# StandaloneAnemometer_RevA.net
KiCad netlist of a schematic drawn in EAGLE
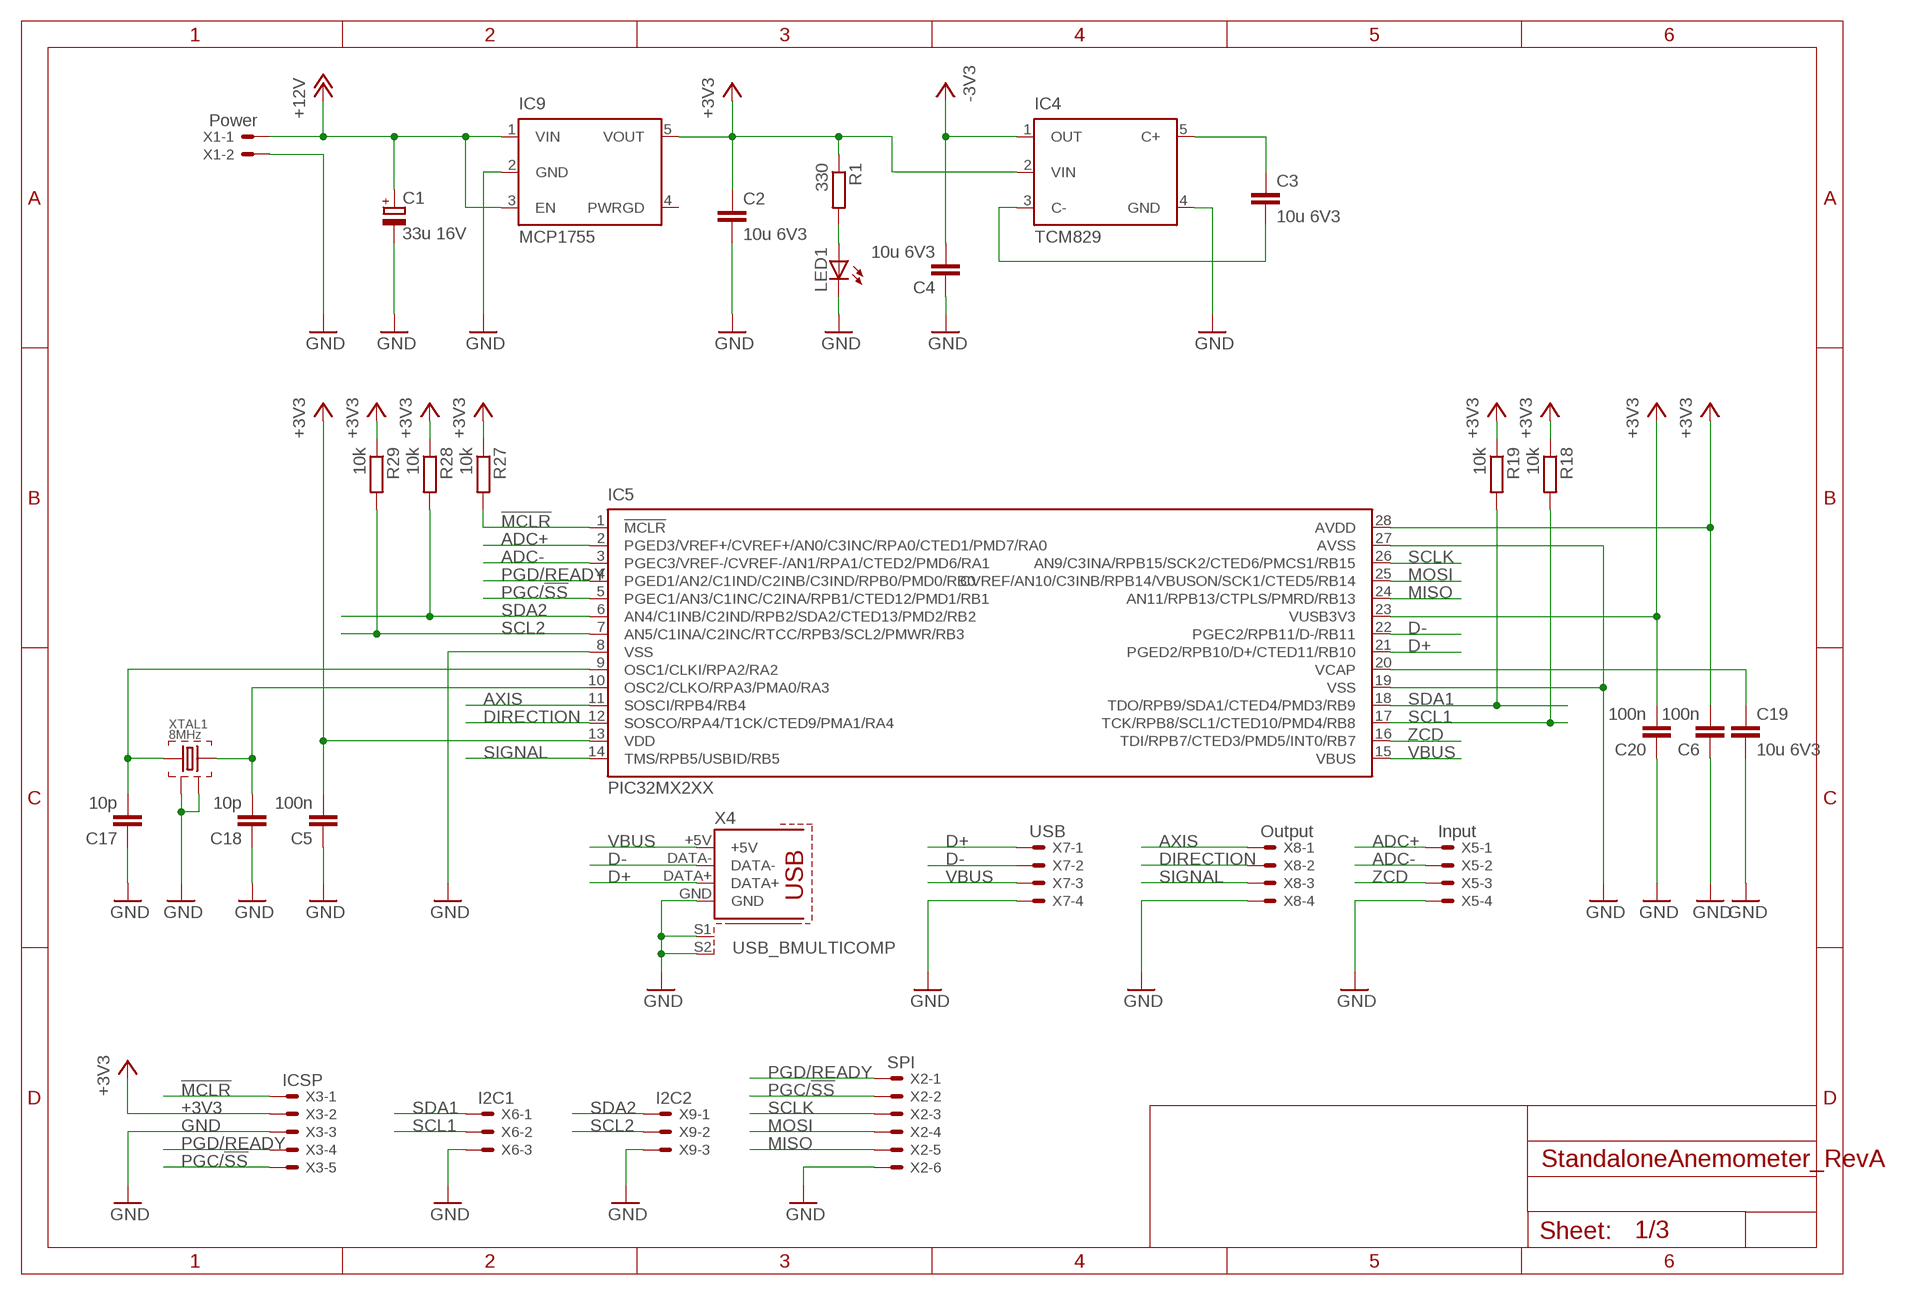
[diagram p0: schematic, sheet 1]
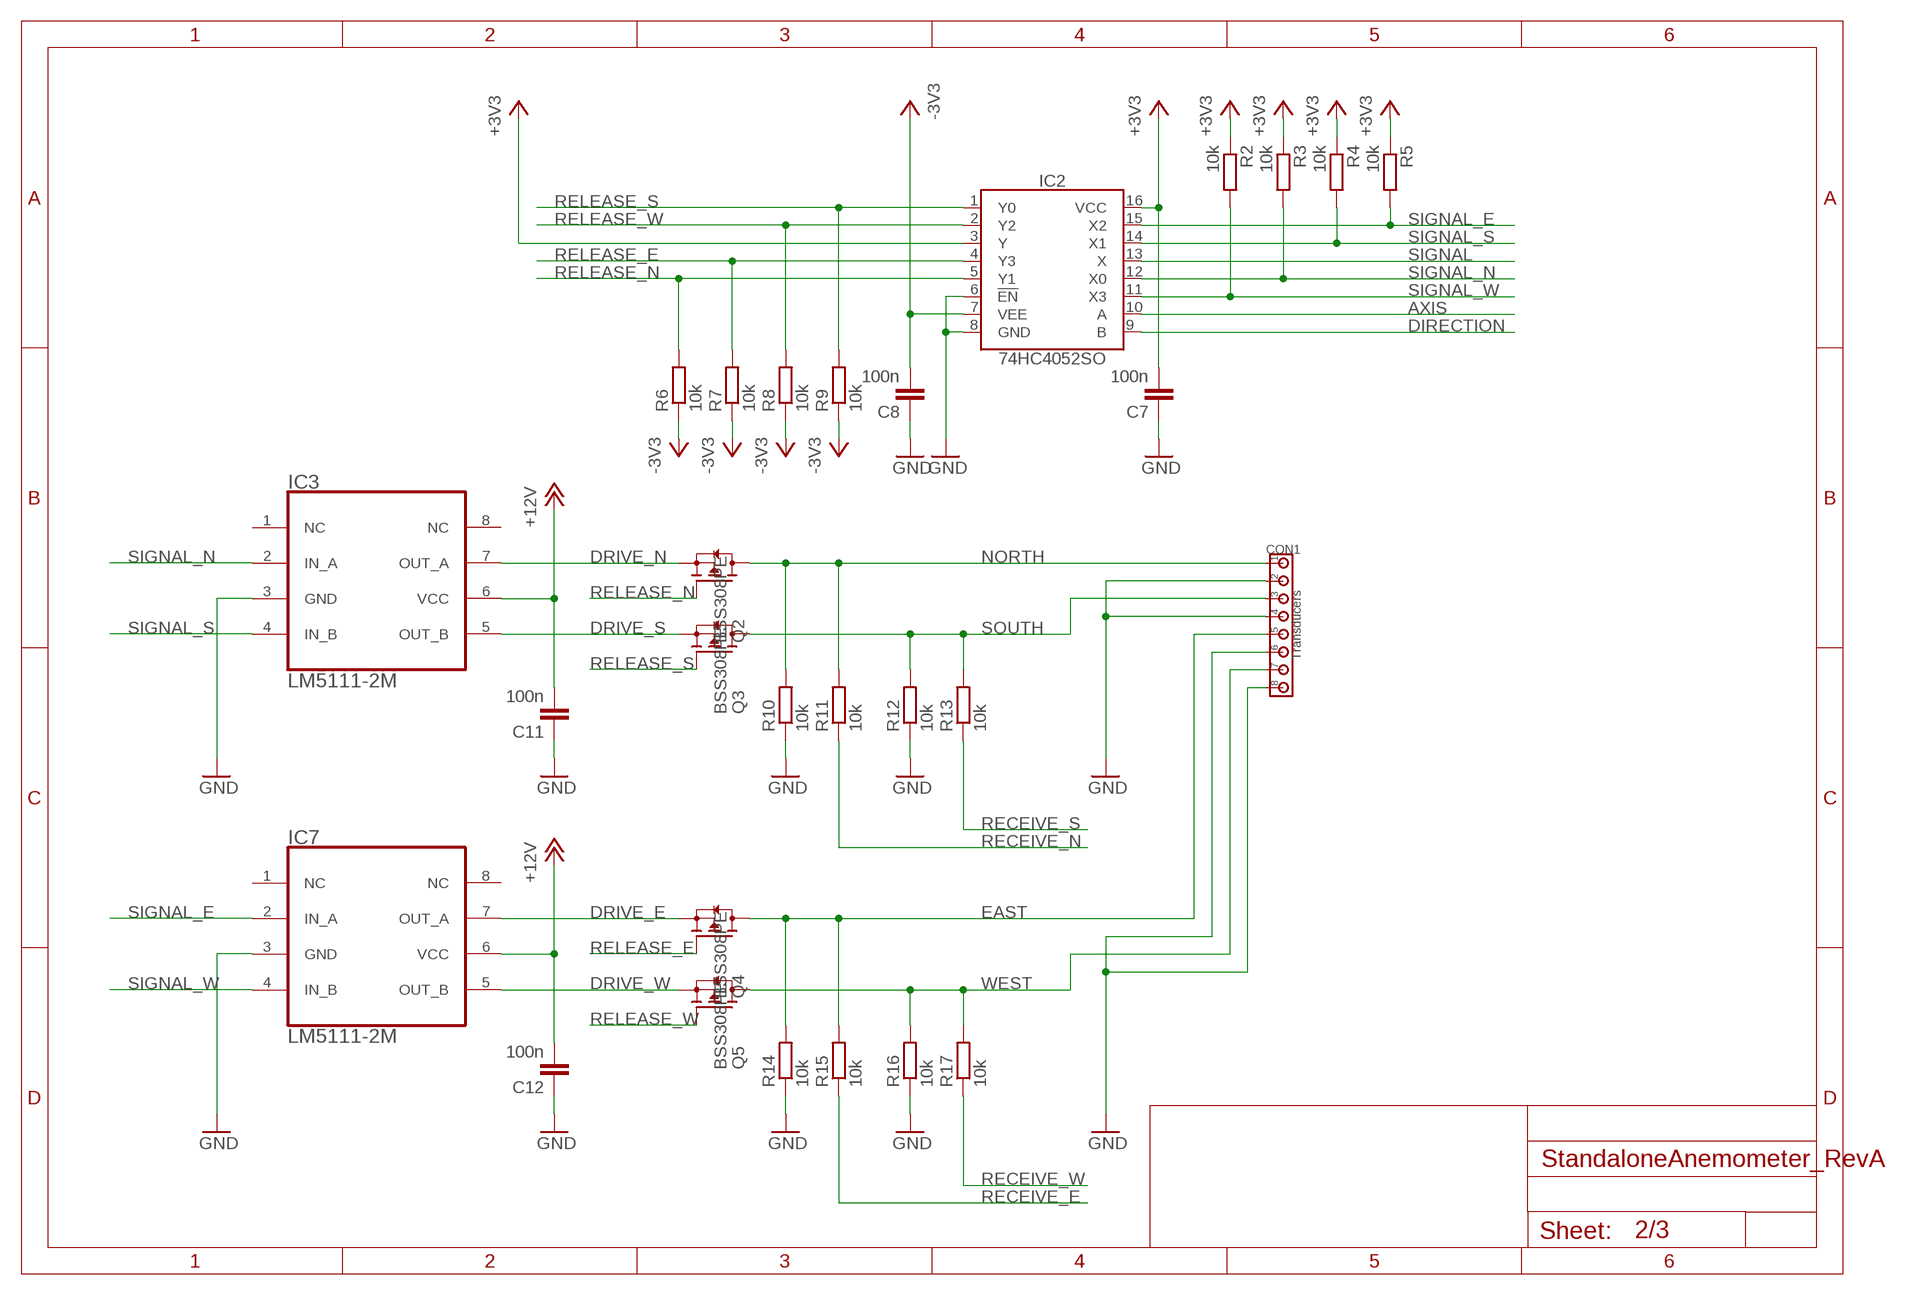
[diagram p1: schematic, sheet 2]
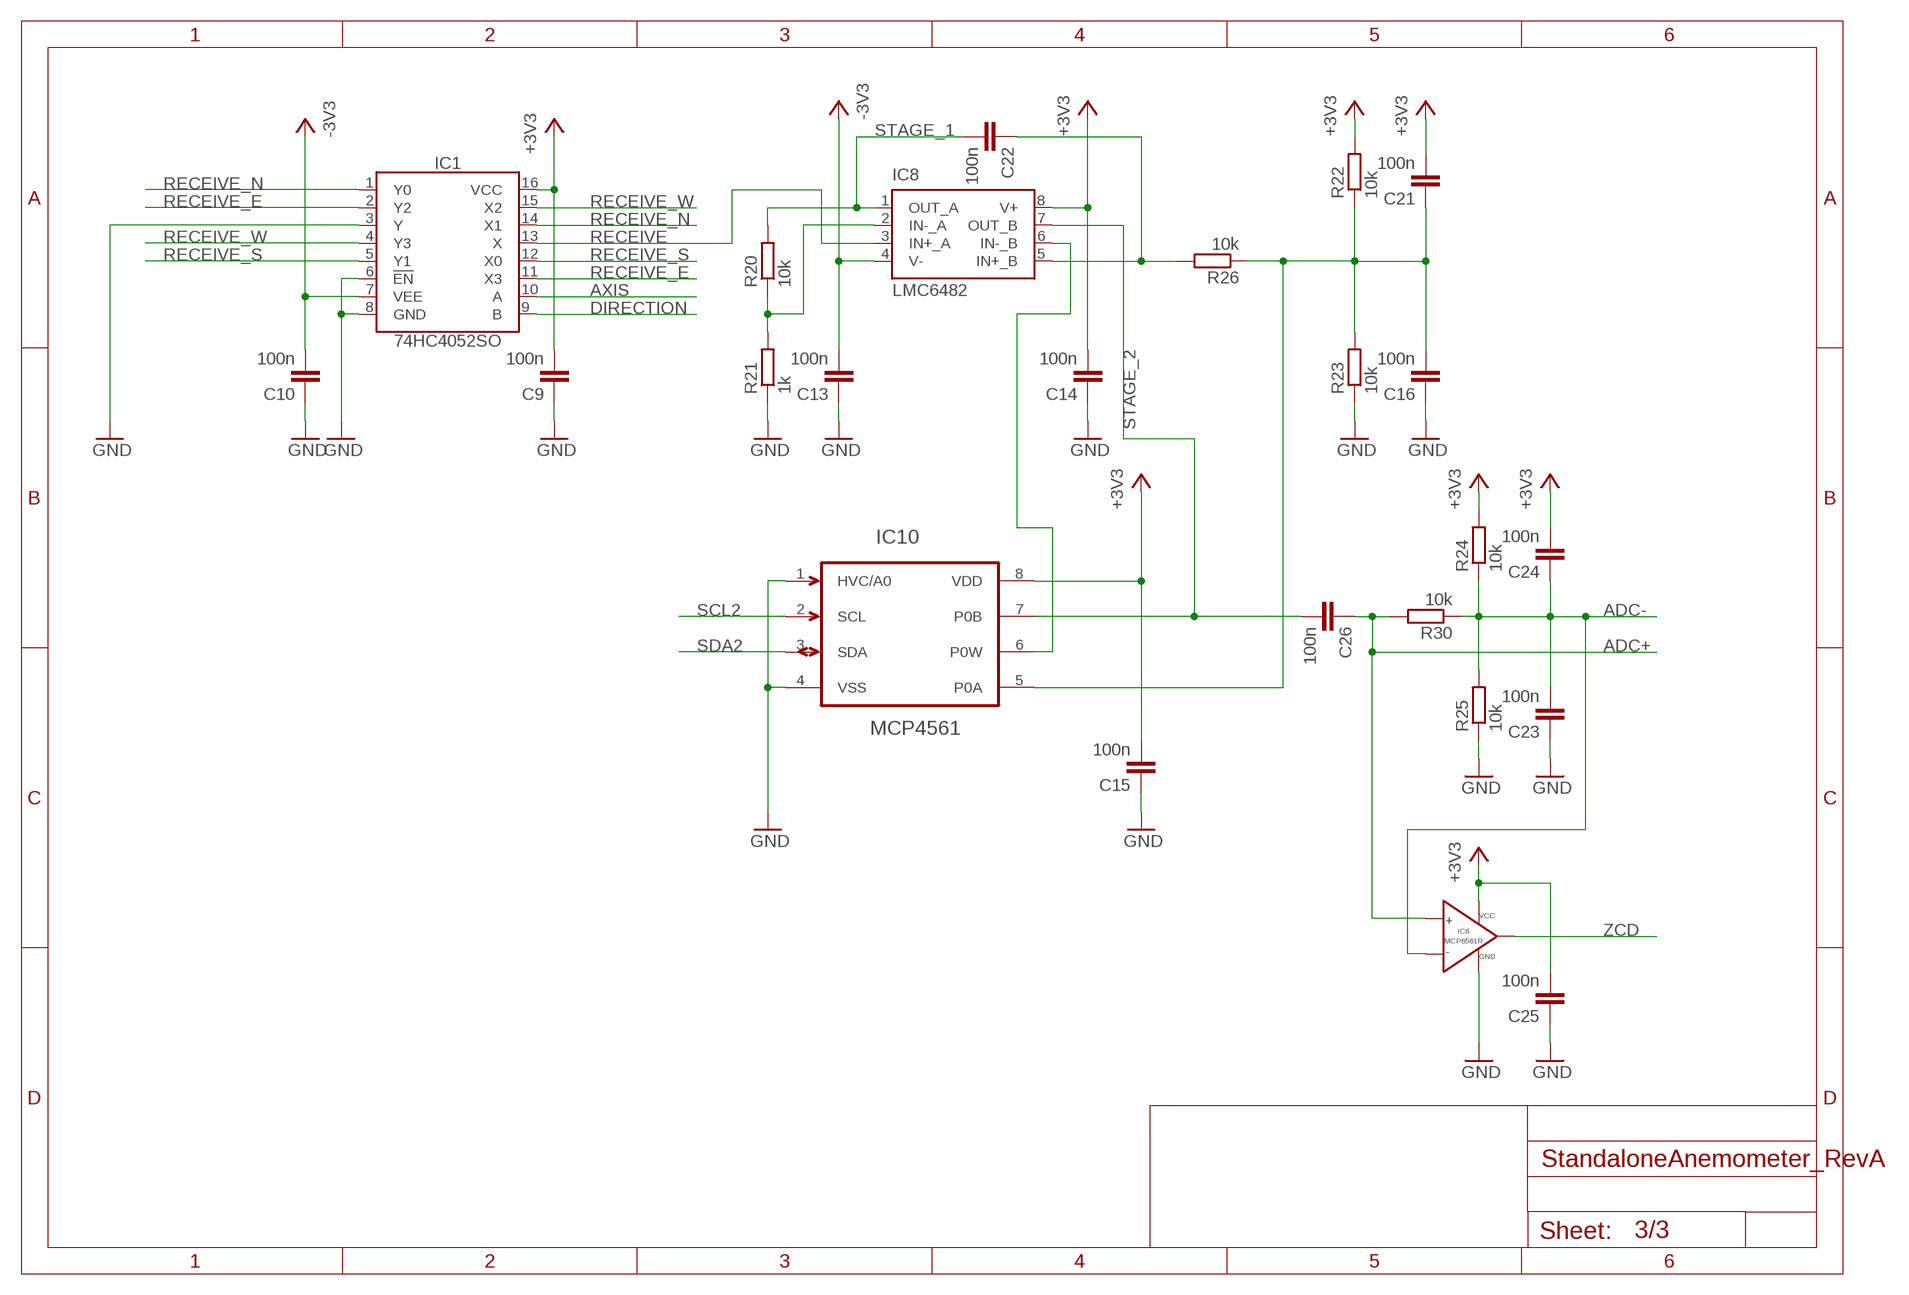
[diagram p2: schematic, sheet 3]

(export (version "E")
  (design (tool "Eeschema 10.0.6"))
  (components
    (comp (ref "C1")
      (value "33u 16V")
      (footprint "eagle-import:SMC_B")
      (libsource (lib "eagle-import") (part "C_POLARIZEDSMC_B"))
    )
    (comp (ref "C2")
      (value "10u 6V3")
      (footprint "eagle-import:C0805")
      (libsource (lib "eagle-import") (part "CC0805"))
    )
    (comp (ref "C3")
      (value "10u 6V3")
      (footprint "eagle-import:C0805")
      (libsource (lib "eagle-import") (part "CC0805"))
    )
    (comp (ref "C4")
      (value "10u 6V3")
      (footprint "eagle-import:C0805")
      (libsource (lib "eagle-import") (part "CC0805"))
    )
    (comp (ref "C5")
      (value "100n")
      (footprint "eagle-import:C0805")
      (libsource (lib "eagle-import") (part "CC0805"))
    )
    (comp (ref "C6")
      (value "100n")
      (footprint "eagle-import:C0805")
      (libsource (lib "eagle-import") (part "CC0805"))
    )
    (comp (ref "C17")
      (value "10p")
      (footprint "eagle-import:C0805")
      (libsource (lib "eagle-import") (part "CC0805"))
    )
    (comp (ref "C18")
      (value "10p")
      (footprint "eagle-import:C0805")
      (libsource (lib "eagle-import") (part "CC0805"))
    )
    (comp (ref "C19")
      (value "10u 6V3")
      (footprint "eagle-import:C0805")
      (libsource (lib "eagle-import") (part "CC0805"))
    )
    (comp (ref "C20")
      (value "100n")
      (footprint "eagle-import:C0805")
      (libsource (lib "eagle-import") (part "CC0805"))
    )
    (comp (ref "IC4")
      (value "TCM829")
      (footprint "eagle-import:SOT-23-5")
      (libsource (lib "eagle-import") (part "TCM829"))
    )
    (comp (ref "IC5")
      (value "PIC32MX2XX")
      (footprint "eagle-import:SO28W")
      (libsource (lib "eagle-import") (part "PIC32MX2XX"))
    )
    (comp (ref "IC9")
      (value "MCP1755")
      (footprint "eagle-import:SOT-23-5")
      (libsource (lib "eagle-import") (part "MCP1755"))
    )
    (comp (ref "LED1")
      (value "LED0805")
      (footprint "eagle-import:LED0805")
      (libsource (lib "eagle-import") (part "LED0805"))
    )
    (comp (ref "R1")
      (value "330")
      (footprint "eagle-import:R0805")
      (libsource (lib "eagle-import") (part "RESISTORR0805"))
    )
    (comp (ref "R18")
      (value "10k")
      (footprint "eagle-import:R0805")
      (libsource (lib "eagle-import") (part "RESISTORR0805"))
    )
    (comp (ref "R19")
      (value "10k")
      (footprint "eagle-import:R0805")
      (libsource (lib "eagle-import") (part "RESISTORR0805"))
    )
    (comp (ref "R27")
      (value "10k")
      (footprint "eagle-import:R0805")
      (libsource (lib "eagle-import") (part "RESISTORR0805"))
    )
    (comp (ref "R28")
      (value "10k")
      (footprint "eagle-import:R0805")
      (libsource (lib "eagle-import") (part "RESISTORR0805"))
    )
    (comp (ref "R29")
      (value "10k")
      (footprint "eagle-import:R0805")
      (libsource (lib "eagle-import") (part "RESISTORR0805"))
    )
    (comp (ref "X1")
      (value "Power")
      (footprint "eagle-import:22-23-2021")
      (fields (field (name "MF") "MOLEX") (field (name "MPN") "22-23-2021"))
      (libsource (lib "eagle-import") (part "22-23-2021100MIL"))
    )
    (comp (ref "X2")
      (value "SPI")
      (footprint "eagle-import:22-23-2061")
      (fields (field (name "MF") "MOLEX") (field (name "MPN") "22-23-2061"))
      (libsource (lib "eagle-import") (part "22-23-2061"))
    )
    (comp (ref "X3")
      (value "ICSP")
      (footprint "eagle-import:22-23-2051")
      (fields (field (name "MF") "MOLEX") (field (name "MPN") "22-23-2051"))
      (libsource (lib "eagle-import") (part "22-23-2051"))
    )
    (comp (ref "X4")
      (value "USB_BMULTICOMP")
      (footprint "eagle-import:USB_B")
      (libsource (lib "eagle-import") (part "USB_BMULTICOMP"))
    )
    (comp (ref "X5")
      (value "Input")
      (footprint "eagle-import:22-23-2041")
      (libsource (lib "eagle-import") (part "22-23-20411MM"))
    )
    (comp (ref "X6")
      (value "I2C1")
      (footprint "eagle-import:22-23-2031")
      (fields (field (name "MF") "MOLEX") (field (name "MPN") "22-23-2031"))
      (libsource (lib "eagle-import") (part "22-23-2031"))
    )
    (comp (ref "X7")
      (value "USB")
      (footprint "eagle-import:22-23-2041")
      (libsource (lib "eagle-import") (part "22-23-20411MM"))
    )
    (comp (ref "X8")
      (value "Output")
      (footprint "eagle-import:22-23-2041")
      (libsource (lib "eagle-import") (part "22-23-20411MM"))
    )
    (comp (ref "X9")
      (value "I2C2")
      (footprint "eagle-import:22-23-2031")
      (fields (field (name "MF") "MOLEX") (field (name "MPN") "22-23-2031"))
      (libsource (lib "eagle-import") (part "22-23-2031"))
    )
    (comp (ref "XTAL1")
      (value "8MHz")
      (footprint "eagle-import:5X3.2MM")
      (libsource (lib "eagle-import") (part "CRYSTAL_SHIELDED"))
    )
    (comp (ref "C9")
      (value "100n")
      (footprint "eagle-import:C0805")
      (libsource (lib "eagle-import") (part "CC0805"))
    )
    (comp (ref "C10")
      (value "100n")
      (footprint "eagle-import:C0805")
      (libsource (lib "eagle-import") (part "CC0805"))
    )
    (comp (ref "C13")
      (value "100n")
      (footprint "eagle-import:C0805")
      (libsource (lib "eagle-import") (part "CC0805"))
    )
    (comp (ref "C14")
      (value "100n")
      (footprint "eagle-import:C0805")
      (libsource (lib "eagle-import") (part "CC0805"))
    )
    (comp (ref "C15")
      (value "100n")
      (footprint "eagle-import:C0805")
      (libsource (lib "eagle-import") (part "CC0805"))
    )
    (comp (ref "C16")
      (value "100n")
      (footprint "eagle-import:C0805")
      (libsource (lib "eagle-import") (part "CC0805"))
    )
    (comp (ref "C21")
      (value "100n")
      (footprint "eagle-import:C0805")
      (libsource (lib "eagle-import") (part "CC0805"))
    )
    (comp (ref "C22")
      (value "100n")
      (footprint "eagle-import:C0805")
      (libsource (lib "eagle-import") (part "CC0805"))
    )
    (comp (ref "C23")
      (value "100n")
      (footprint "eagle-import:C0805")
      (libsource (lib "eagle-import") (part "CC0805"))
    )
    (comp (ref "C24")
      (value "100n")
      (footprint "eagle-import:C0805")
      (libsource (lib "eagle-import") (part "CC0805"))
    )
    (comp (ref "C25")
      (value "100n")
      (footprint "eagle-import:C0805")
      (libsource (lib "eagle-import") (part "CC0805"))
    )
    (comp (ref "C26")
      (value "100n")
      (footprint "eagle-import:C0805")
      (libsource (lib "eagle-import") (part "CC0805"))
    )
    (comp (ref "IC1")
      (value "74HC4052SO")
      (footprint "eagle-import:SO16")
      (libsource (lib "eagle-import") (part "74HC4052SO"))
    )
    (comp (ref "IC6")
      (value "MCP6561R")
      (footprint "eagle-import:SOT-23-5")
      (libsource (lib "eagle-import") (part "MCP6561R"))
    )
    (comp (ref "IC8")
      (value "LMC6482")
      (footprint "eagle-import:SOIC8")
      (libsource (lib "eagle-import") (part "LMC6482"))
    )
    (comp (ref "IC10")
      (value "MCP4561")
      (footprint "eagle-import:MSOP")
      (libsource (lib "eagle-import") (part "MCP4561MSOP"))
    )
    (comp (ref "R20")
      (value "10k")
      (footprint "eagle-import:R0805")
      (libsource (lib "eagle-import") (part "RESISTORR0805"))
    )
    (comp (ref "R21")
      (value "1k")
      (footprint "eagle-import:R0805")
      (libsource (lib "eagle-import") (part "RESISTORR0805"))
    )
    (comp (ref "R22")
      (value "10k")
      (footprint "eagle-import:R0805")
      (libsource (lib "eagle-import") (part "RESISTORR0805"))
    )
    (comp (ref "R23")
      (value "10k")
      (footprint "eagle-import:R0805")
      (libsource (lib "eagle-import") (part "RESISTORR0805"))
    )
    (comp (ref "R24")
      (value "10k")
      (footprint "eagle-import:R0805")
      (libsource (lib "eagle-import") (part "RESISTORR0805"))
    )
    (comp (ref "R25")
      (value "10k")
      (footprint "eagle-import:R0805")
      (libsource (lib "eagle-import") (part "RESISTORR0805"))
    )
    (comp (ref "R26")
      (value "10k")
      (footprint "eagle-import:R0805")
      (libsource (lib "eagle-import") (part "RESISTORR0805"))
    )
    (comp (ref "R30")
      (value "10k")
      (footprint "eagle-import:R0805")
      (libsource (lib "eagle-import") (part "RESISTORR0805"))
    )
    (comp (ref "C7")
      (value "100n")
      (footprint "eagle-import:C0805")
      (libsource (lib "eagle-import") (part "CC0805"))
    )
    (comp (ref "C8")
      (value "100n")
      (footprint "eagle-import:C0805")
      (libsource (lib "eagle-import") (part "CC0805"))
    )
    (comp (ref "C11")
      (value "100n")
      (footprint "eagle-import:C0805")
      (libsource (lib "eagle-import") (part "CC0805"))
    )
    (comp (ref "C12")
      (value "100n")
      (footprint "eagle-import:C0805")
      (libsource (lib "eagle-import") (part "CC0805"))
    )
    (comp (ref "CON1")
      (value "Transducers")
      (footprint "eagle-import:3.5MM_8X")
      (libsource (lib "eagle-import") (part "CON_8X3.5MM"))
    )
    (comp (ref "IC2")
      (value "74HC4052SO")
      (footprint "eagle-import:SO16")
      (libsource (lib "eagle-import") (part "74HC4052SO"))
    )
    (comp (ref "IC3")
      (value "LM5111-2M")
      (footprint "eagle-import:SOIC8")
      (libsource (lib "eagle-import") (part "LM5111"))
    )
    (comp (ref "IC7")
      (value "LM5111-2M")
      (footprint "eagle-import:SOIC8")
      (libsource (lib "eagle-import") (part "LM5111"))
    )
    (comp (ref "Q2")
      (value "BSS308PE")
      (footprint "eagle-import:SOT23")
      (libsource (lib "eagle-import") (part "P-FET"))
    )
    (comp (ref "Q3")
      (value "BSS308PE")
      (footprint "eagle-import:SOT23")
      (libsource (lib "eagle-import") (part "P-FET"))
    )
    (comp (ref "Q4")
      (value "BSS308PE")
      (footprint "eagle-import:SOT23")
      (libsource (lib "eagle-import") (part "P-FET"))
    )
    (comp (ref "Q5")
      (value "BSS308PE")
      (footprint "eagle-import:SOT23")
      (libsource (lib "eagle-import") (part "P-FET"))
    )
    (comp (ref "R2")
      (value "10k")
      (footprint "eagle-import:R0805")
      (libsource (lib "eagle-import") (part "RESISTORR0805"))
    )
    (comp (ref "R3")
      (value "10k")
      (footprint "eagle-import:R0805")
      (libsource (lib "eagle-import") (part "RESISTORR0805"))
    )
    (comp (ref "R4")
      (value "10k")
      (footprint "eagle-import:R0805")
      (libsource (lib "eagle-import") (part "RESISTORR0805"))
    )
    (comp (ref "R5")
      (value "10k")
      (footprint "eagle-import:R0805")
      (libsource (lib "eagle-import") (part "RESISTORR0805"))
    )
    (comp (ref "R6")
      (value "10k")
      (footprint "eagle-import:R0805")
      (libsource (lib "eagle-import") (part "RESISTORR0805"))
    )
    (comp (ref "R7")
      (value "10k")
      (footprint "eagle-import:R0805")
      (libsource (lib "eagle-import") (part "RESISTORR0805"))
    )
    (comp (ref "R8")
      (value "10k")
      (footprint "eagle-import:R0805")
      (libsource (lib "eagle-import") (part "RESISTORR0805"))
    )
    (comp (ref "R9")
      (value "10k")
      (footprint "eagle-import:R0805")
      (libsource (lib "eagle-import") (part "RESISTORR0805"))
    )
    (comp (ref "R10")
      (value "10k")
      (footprint "eagle-import:R0805")
      (libsource (lib "eagle-import") (part "RESISTORR0805"))
    )
    (comp (ref "R11")
      (value "10k")
      (footprint "eagle-import:R0805")
      (libsource (lib "eagle-import") (part "RESISTORR0805"))
    )
    (comp (ref "R12")
      (value "10k")
      (footprint "eagle-import:R0805")
      (libsource (lib "eagle-import") (part "RESISTORR0805"))
    )
    (comp (ref "R13")
      (value "10k")
      (footprint "eagle-import:R0805")
      (libsource (lib "eagle-import") (part "RESISTORR0805"))
    )
    (comp (ref "R14")
      (value "10k")
      (footprint "eagle-import:R0805")
      (libsource (lib "eagle-import") (part "RESISTORR0805"))
    )
    (comp (ref "R15")
      (value "10k")
      (footprint "eagle-import:R0805")
      (libsource (lib "eagle-import") (part "RESISTORR0805"))
    )
    (comp (ref "R16")
      (value "10k")
      (footprint "eagle-import:R0805")
      (libsource (lib "eagle-import") (part "RESISTORR0805"))
    )
    (comp (ref "R17")
      (value "10k")
      (footprint "eagle-import:R0805")
      (libsource (lib "eagle-import") (part "RESISTORR0805"))
    )
  )
  (nets
    (net (code "1") (name "+3V3") (class "Default")
      (node (ref "C14") (pin "2") (pinfunction "2_2") (pintype "passive"))
      (node (ref "C15") (pin "2") (pinfunction "2_2") (pintype "passive"))
      (node (ref "C2") (pin "1") (pinfunction "1_1") (pintype "passive"))
      (node (ref "C20") (pin "2") (pinfunction "2_2") (pintype "passive"))
      (node (ref "C21") (pin "2") (pinfunction "2_2") (pintype "passive"))
      (node (ref "C24") (pin "2") (pinfunction "2_2") (pintype "passive"))
      (node (ref "C25") (pin "2") (pinfunction "2_2") (pintype "passive"))
      (node (ref "C5") (pin "2") (pinfunction "2_2") (pintype "passive"))
      (node (ref "C6") (pin "2") (pinfunction "2_2") (pintype "passive"))
      (node (ref "C7") (pin "2") (pinfunction "2_2") (pintype "passive"))
      (node (ref "C9") (pin "2") (pinfunction "2_2") (pintype "passive"))
      (node (ref "IC1") (pin "16") (pinfunction "VCC_16") (pintype "power_in"))
      (node (ref "IC10") (pin "8") (pinfunction "VDD_8") (pintype "power_in"))
      (node (ref "IC2") (pin "16") (pinfunction "VCC_16") (pintype "power_in"))
      (node (ref "IC2") (pin "3") (pinfunction "Y_3") (pintype "input"))
      (node (ref "IC4") (pin "2") (pinfunction "VIN_2") (pintype "passive"))
      (node (ref "IC5") (pin "13") (pinfunction "VDD_13") (pintype "bidirectional"))
      (node (ref "IC5") (pin "23") (pinfunction "VUSB3V3_23") (pintype "bidirectional"))
      (node (ref "IC5") (pin "28") (pinfunction "AVDD_28") (pintype "bidirectional"))
      (node (ref "IC6") (pin "2") (pinfunction "VCC_2") (pintype "input"))
      (node (ref "IC8") (pin "8") (pinfunction "V+_8") (pintype "input"))
      (node (ref "IC9") (pin "5") (pinfunction "VOUT_5") (pintype "output"))
      (node (ref "R1") (pin "1") (pinfunction "1_1") (pintype "passive"))
      (node (ref "R18") (pin "1") (pinfunction "1_1") (pintype "passive"))
      (node (ref "R19") (pin "1") (pinfunction "1_1") (pintype "passive"))
      (node (ref "R2") (pin "1") (pinfunction "1_1") (pintype "passive"))
      (node (ref "R22") (pin "2") (pinfunction "2_2") (pintype "passive"))
      (node (ref "R24") (pin "2") (pinfunction "2_2") (pintype "passive"))
      (node (ref "R27") (pin "1") (pinfunction "1_1") (pintype "passive"))
      (node (ref "R28") (pin "1") (pinfunction "1_1") (pintype "passive"))
      (node (ref "R29") (pin "1") (pinfunction "1_1") (pintype "passive"))
      (node (ref "R3") (pin "1") (pinfunction "1_1") (pintype "passive"))
      (node (ref "R4") (pin "1") (pinfunction "1_1") (pintype "passive"))
      (node (ref "R5") (pin "1") (pinfunction "1_1") (pintype "passive"))
      (node (ref "X3") (pin "2") (pinfunction "S_2") (pintype "passive"))
    )
    (net (code "2") (name "+12V") (class "Default")
      (node (ref "C1") (pin "+") (pinfunction "+_+") (pintype "passive"))
      (node (ref "C11") (pin "2") (pinfunction "2_2") (pintype "passive"))
      (node (ref "C12") (pin "2") (pinfunction "2_2") (pintype "passive"))
      (node (ref "IC3") (pin "6") (pinfunction "VCC_6") (pintype "input"))
      (node (ref "IC7") (pin "6") (pinfunction "VCC_6") (pintype "input"))
      (node (ref "IC9") (pin "1") (pinfunction "VIN_1") (pintype "passive"))
      (node (ref "IC9") (pin "3") (pinfunction "EN_3") (pintype "passive"))
      (node (ref "X1") (pin "1") (pinfunction "S_1") (pintype "passive"))
    )
    (net (code "3") (name "-3V3") (class "Default")
      (node (ref "C10") (pin "2") (pinfunction "2_2") (pintype "passive"))
      (node (ref "C13") (pin "2") (pinfunction "2_2") (pintype "passive"))
      (node (ref "C4") (pin "2") (pinfunction "2_2") (pintype "passive"))
      (node (ref "C8") (pin "2") (pinfunction "2_2") (pintype "passive"))
      (node (ref "IC1") (pin "7") (pinfunction "VEE_7") (pintype "bidirectional"))
      (node (ref "IC2") (pin "7") (pinfunction "VEE_7") (pintype "bidirectional"))
      (node (ref "IC4") (pin "1") (pinfunction "OUT_1") (pintype "passive"))
      (node (ref "IC8") (pin "4") (pinfunction "V-_4") (pintype "power_in"))
      (node (ref "R6") (pin "1") (pinfunction "1_1") (pintype "passive"))
      (node (ref "R7") (pin "1") (pinfunction "1_1") (pintype "passive"))
      (node (ref "R8") (pin "1") (pinfunction "1_1") (pintype "passive"))
      (node (ref "R9") (pin "1") (pinfunction "1_1") (pintype "passive"))
    )
    (net (code "4") (name "ADC+") (class "Default")
      (node (ref "C26") (pin "1") (pinfunction "1_1") (pintype "passive"))
      (node (ref "IC5") (pin "2") (pinfunction "PGED3/VREF+/CVREF+/AN0/C3INC/RPA0/CTED1/PMD7/RA0_2") (pintype "bidirectional"))
      (node (ref "IC6") (pin "3") (pinfunction "VIN+_3") (pintype "input"))
      (node (ref "R30") (pin "2") (pinfunction "2_2") (pintype "passive"))
      (node (ref "X5") (pin "1") (pinfunction "S_1") (pintype "passive"))
    )
    (net (code "5") (name "ADC-") (class "Default")
      (node (ref "C23") (pin "2") (pinfunction "2_2") (pintype "passive"))
      (node (ref "C24") (pin "1") (pinfunction "1_1") (pintype "passive"))
      (node (ref "IC5") (pin "3") (pinfunction "PGEC3/VREF-/CVREF-/AN1/RPA1/CTED2/PMD6/RA1_3") (pintype "bidirectional"))
      (node (ref "IC6") (pin "4") (pinfunction "VIN-_4") (pintype "input"))
      (node (ref "R24") (pin "1") (pinfunction "1_1") (pintype "passive"))
      (node (ref "R25") (pin "2") (pinfunction "2_2") (pintype "passive"))
      (node (ref "R30") (pin "1") (pinfunction "1_1") (pintype "passive"))
      (node (ref "X5") (pin "2") (pinfunction "S_2") (pintype "passive"))
    )
    (net (code "6") (name "AXIS") (class "Default")
      (node (ref "IC1") (pin "10") (pinfunction "A_10") (pintype "bidirectional"))
      (node (ref "IC2") (pin "10") (pinfunction "A_10") (pintype "bidirectional"))
      (node (ref "IC5") (pin "11") (pinfunction "SOSCI/RPB4/RB4_11") (pintype "bidirectional"))
      (node (ref "X8") (pin "1") (pinfunction "S_1") (pintype "passive"))
    )
    (net (code "7") (name "D+") (class "Default")
      (node (ref "IC5") (pin "21") (pinfunction "PGED2/RPB10/D+/CTED11/RB10_21") (pintype "bidirectional"))
      (node (ref "X4") (pin "DATA+") (pinfunction "DATA+_DATA+") (pintype "passive"))
      (node (ref "X7") (pin "1") (pinfunction "S_1") (pintype "passive"))
    )
    (net (code "8") (name "D-") (class "Default")
      (node (ref "IC5") (pin "22") (pinfunction "PGEC2/RPB11/D-/RB11_22") (pintype "bidirectional"))
      (node (ref "X4") (pin "DATA-") (pinfunction "DATA-_DATA-") (pintype "passive"))
      (node (ref "X7") (pin "2") (pinfunction "S_2") (pintype "passive"))
    )
    (net (code "9") (name "DIRECTION") (class "Default")
      (node (ref "IC1") (pin "9") (pinfunction "B_9") (pintype "bidirectional"))
      (node (ref "IC2") (pin "9") (pinfunction "B_9") (pintype "bidirectional"))
      (node (ref "IC5") (pin "12") (pinfunction "SOSCO/RPA4/T1CK/CTED9/PMA1/RA4_12") (pintype "bidirectional"))
      (node (ref "X8") (pin "2") (pinfunction "S_2") (pintype "passive"))
    )
    (net (code "10") (name "DRIVE_E") (class "Default")
      (node (ref "IC7") (pin "7") (pinfunction "OUT_A_7") (pintype "input"))
      (node (ref "Q4") (pin "2") (pinfunction "S_2") (pintype "passive"))
    )
    (net (code "11") (name "DRIVE_N") (class "Default")
      (node (ref "IC3") (pin "7") (pinfunction "OUT_A_7") (pintype "input"))
      (node (ref "Q2") (pin "2") (pinfunction "S_2") (pintype "passive"))
    )
    (net (code "12") (name "DRIVE_S") (class "Default")
      (node (ref "IC3") (pin "5") (pinfunction "OUT_B_5") (pintype "bidirectional"))
      (node (ref "Q3") (pin "2") (pinfunction "S_2") (pintype "passive"))
    )
    (net (code "13") (name "DRIVE_W") (class "Default")
      (node (ref "IC7") (pin "5") (pinfunction "OUT_B_5") (pintype "bidirectional"))
      (node (ref "Q5") (pin "2") (pinfunction "S_2") (pintype "passive"))
    )
    (net (code "14") (name "EAST") (class "Default")
      (node (ref "CON1") (pin "5") (pinfunction "P$5_5") (pintype "passive"))
      (node (ref "Q4") (pin "3") (pinfunction "D_3") (pintype "passive"))
      (node (ref "R14") (pin "2") (pinfunction "2_2") (pintype "passive"))
      (node (ref "R15") (pin "2") (pinfunction "2_2") (pintype "passive"))
    )
    (net (code "15") (name "GND") (class "Default")
      (node (ref "C1") (pin "-") (pinfunction "-_-") (pintype "passive"))
      (node (ref "C10") (pin "1") (pinfunction "1_1") (pintype "passive"))
      (node (ref "C11") (pin "1") (pinfunction "1_1") (pintype "passive"))
      (node (ref "C12") (pin "1") (pinfunction "1_1") (pintype "passive"))
      (node (ref "C13") (pin "1") (pinfunction "1_1") (pintype "passive"))
      (node (ref "C14") (pin "1") (pinfunction "1_1") (pintype "passive"))
      (node (ref "C15") (pin "1") (pinfunction "1_1") (pintype "passive"))
      (node (ref "C16") (pin "1") (pinfunction "1_1") (pintype "passive"))
      (node (ref "C17") (pin "1") (pinfunction "1_1") (pintype "passive"))
      (node (ref "C18") (pin "1") (pinfunction "1_1") (pintype "passive"))
      (node (ref "C19") (pin "2") (pinfunction "2_2") (pintype "passive"))
      (node (ref "C2") (pin "2") (pinfunction "2_2") (pintype "passive"))
      (node (ref "C20") (pin "1") (pinfunction "1_1") (pintype "passive"))
      (node (ref "C23") (pin "1") (pinfunction "1_1") (pintype "passive"))
      (node (ref "C25") (pin "1") (pinfunction "1_1") (pintype "passive"))
      (node (ref "C4") (pin "1") (pinfunction "1_1") (pintype "passive"))
      (node (ref "C5") (pin "1") (pinfunction "1_1") (pintype "passive"))
      (node (ref "C6") (pin "1") (pinfunction "1_1") (pintype "passive"))
      (node (ref "C7") (pin "1") (pinfunction "1_1") (pintype "passive"))
      (node (ref "C8") (pin "1") (pinfunction "1_1") (pintype "passive"))
      (node (ref "C9") (pin "1") (pinfunction "1_1") (pintype "passive"))
      (node (ref "CON1") (pin "2") (pinfunction "P$2_2") (pintype "passive"))
      (node (ref "CON1") (pin "4") (pinfunction "P$4_4") (pintype "passive"))
      (node (ref "CON1") (pin "6") (pinfunction "P$6_6") (pintype "passive"))
      (node (ref "CON1") (pin "8") (pinfunction "P$8_8") (pintype "passive"))
      (node (ref "IC1") (pin "3") (pinfunction "Y_3") (pintype "input"))
      (node (ref "IC1") (pin "6") (pinfunction "~{EN}_6") (pintype "input"))
      (node (ref "IC1") (pin "8") (pinfunction "GND_8") (pintype "output"))
      (node (ref "IC10") (pin "1") (pinfunction "HVC/A0_1") (pintype "input"))
      (node (ref "IC10") (pin "4") (pinfunction "VSS_4") (pintype "power_in"))
      (node (ref "IC2") (pin "6") (pinfunction "~{EN}_6") (pintype "input"))
      (node (ref "IC2") (pin "8") (pinfunction "GND_8") (pintype "output"))
      (node (ref "IC3") (pin "3") (pinfunction "GND_3") (pintype "input"))
      (node (ref "IC4") (pin "4") (pinfunction "GND_4") (pintype "output"))
      (node (ref "IC5") (pin "19") (pinfunction "VSS_19") (pintype "power_in"))
      (node (ref "IC5") (pin "27") (pinfunction "AVSS_27") (pintype "bidirectional"))
      (node (ref "IC5") (pin "8") (pinfunction "VSS_8") (pintype "power_in"))
      (node (ref "IC6") (pin "5") (pinfunction "GND_5") (pintype "input"))
      (node (ref "IC7") (pin "3") (pinfunction "GND_3") (pintype "input"))
      (node (ref "IC9") (pin "2") (pinfunction "GND_2") (pintype "passive"))
      (node (ref "LED1") (pin "C") (pinfunction "C_C") (pintype "passive"))
      (node (ref "R10") (pin "1") (pinfunction "1_1") (pintype "passive"))
      (node (ref "R12") (pin "1") (pinfunction "1_1") (pintype "passive"))
      (node (ref "R14") (pin "1") (pinfunction "1_1") (pintype "passive"))
      (node (ref "R16") (pin "1") (pinfunction "1_1") (pintype "passive"))
      (node (ref "R21") (pin "1") (pinfunction "1_1") (pintype "passive"))
      (node (ref "R23") (pin "1") (pinfunction "1_1") (pintype "passive"))
      (node (ref "R25") (pin "1") (pinfunction "1_1") (pintype "passive"))
      (node (ref "X1") (pin "2") (pinfunction "S_2") (pintype "passive"))
      (node (ref "X2") (pin "6") (pinfunction "S_6") (pintype "passive"))
      (node (ref "X3") (pin "3") (pinfunction "S_3") (pintype "passive"))
      (node (ref "X4") (pin "GND") (pinfunction "GND_GND") (pintype "passive"))
      (node (ref "X4") (pin "S1") (pinfunction "S1_S1") (pintype "passive"))
      (node (ref "X4") (pin "S2") (pinfunction "S2_S2") (pintype "passive"))
      (node (ref "X5") (pin "4") (pinfunction "S_4") (pintype "passive"))
      (node (ref "X6") (pin "3") (pinfunction "S_3") (pintype "passive"))
      (node (ref "X7") (pin "4") (pinfunction "S_4") (pintype "passive"))
      (node (ref "X8") (pin "4") (pinfunction "S_4") (pintype "passive"))
      (node (ref "X9") (pin "3") (pinfunction "S_3") (pintype "passive"))
      (node (ref "XTAL1") (pin "2") (pinfunction "2_2") (pintype "passive"))
      (node (ref "XTAL1") (pin "4") (pinfunction "4_4") (pintype "passive"))
    )
    (net (code "16") (name "MISO") (class "Default")
      (node (ref "IC5") (pin "24") (pinfunction "AN11/RPB13/CTPLS/PMRD/RB13_24") (pintype "bidirectional"))
      (node (ref "X2") (pin "5") (pinfunction "S_5") (pintype "passive"))
    )
    (net (code "17") (name "MOSI") (class "Default")
      (node (ref "IC5") (pin "25") (pinfunction "CVREF/AN10/C3INB/RPB14/VBUSON/SCK1/CTED5/RB14_25") (pintype "bidirectional"))
      (node (ref "X2") (pin "4") (pinfunction "S_4") (pintype "passive"))
    )
    (net (code "18") (name "NORTH") (class "Default")
      (node (ref "CON1") (pin "1") (pinfunction "P$1_1") (pintype "passive"))
      (node (ref "Q2") (pin "3") (pinfunction "D_3") (pintype "passive"))
      (node (ref "R10") (pin "2") (pinfunction "2_2") (pintype "passive"))
      (node (ref "R11") (pin "2") (pinfunction "2_2") (pintype "passive"))
    )
    (net (code "19") (name "Net-(IC4-C+)") (class "Default")
      (node (ref "C3") (pin "1") (pinfunction "1_1") (pintype "passive"))
      (node (ref "IC4") (pin "5") (pinfunction "C+_5") (pintype "output"))
    )
    (net (code "20") (name "Net-(IC4-C-)") (class "Default")
      (node (ref "C3") (pin "2") (pinfunction "2_2") (pintype "passive"))
      (node (ref "IC4") (pin "3") (pinfunction "C-_3") (pintype "passive"))
    )
    (net (code "21") (name "Net-(IC5-OSC1{slash}CLKI{slash}RPA2{slash}RA2)") (class "Default")
      (node (ref "C17") (pin "2") (pinfunction "2_2") (pintype "passive"))
      (node (ref "IC5") (pin "9") (pinfunction "OSC1/CLKI/RPA2/RA2_9") (pintype "bidirectional"))
      (node (ref "XTAL1") (pin "1") (pinfunction "1_1") (pintype "passive"))
    )
    (net (code "22") (name "Net-(IC5-OSC2{slash}CLKO{slash}RPA3{slash}PMA0{slash}RA3)") (class "Default")
      (node (ref "C18") (pin "2") (pinfunction "2_2") (pintype "passive"))
      (node (ref "IC5") (pin "10") (pinfunction "OSC2/CLKO/RPA3/PMA0/RA3_10") (pintype "bidirectional"))
      (node (ref "XTAL1") (pin "3") (pinfunction "3_3") (pintype "passive"))
    )
    (net (code "23") (name "Net-(IC5-VCAP)") (class "Default")
      (node (ref "C19") (pin "1") (pinfunction "1_1") (pintype "passive"))
      (node (ref "IC5") (pin "20") (pinfunction "VCAP_20") (pintype "power_in"))
    )
    (net (code "24") (name "Net-(IC8-IN+_B)") (class "Default")
      (node (ref "C22") (pin "1") (pinfunction "1_1") (pintype "passive"))
      (node (ref "IC8") (pin "5") (pinfunction "IN+_B_5") (pintype "passive"))
      (node (ref "R26") (pin "2") (pinfunction "2_2") (pintype "passive"))
    )
    (net (code "25") (name "Net-(IC8-IN-_A)") (class "Default")
      (node (ref "IC8") (pin "2") (pinfunction "IN-_A_2") (pintype "input"))
      (node (ref "R20") (pin "1") (pinfunction "1_1") (pintype "passive"))
      (node (ref "R21") (pin "2") (pinfunction "2_2") (pintype "passive"))
    )
    (net (code "26") (name "Net-(IC10-P0A)") (class "Default")
      (node (ref "C16") (pin "2") (pinfunction "2_2") (pintype "passive"))
      (node (ref "C21") (pin "1") (pinfunction "1_1") (pintype "passive"))
      (node (ref "IC10") (pin "5") (pinfunction "P0A_5") (pintype "passive"))
      (node (ref "R22") (pin "1") (pinfunction "1_1") (pintype "passive"))
      (node (ref "R23") (pin "2") (pinfunction "2_2") (pintype "passive"))
      (node (ref "R26") (pin "1") (pinfunction "1_1") (pintype "passive"))
    )
    (net (code "27") (name "Net-(IC10-P0W)") (class "Default")
      (node (ref "IC10") (pin "6") (pinfunction "P0W_6") (pintype "passive"))
      (node (ref "IC8") (pin "6") (pinfunction "IN-_B_6") (pintype "passive"))
    )
    (net (code "28") (name "Net-(LED1-PadA)") (class "Default")
      (node (ref "LED1") (pin "A") (pinfunction "A_A") (pintype "passive"))
      (node (ref "R1") (pin "2") (pinfunction "2_2") (pintype "passive"))
    )
    (net (code "29") (name "PGC{slash}~{SS}") (class "Default")
      (node (ref "IC5") (pin "5") (pinfunction "PGEC1/AN3/C1INC/C2INA/RPB1/CTED12/PMD1/RB1_5") (pintype "bidirectional"))
      (node (ref "X2") (pin "2") (pinfunction "S_2") (pintype "passive"))
      (node (ref "X3") (pin "5") (pinfunction "S_5") (pintype "passive"))
    )
    (net (code "30") (name "PGD{slash}READY") (class "Default")
      (node (ref "IC5") (pin "4") (pinfunction "PGED1/AN2/C1IND/C2INB/C3IND/RPB0/PMD0/RB0_4") (pintype "bidirectional"))
      (node (ref "X2") (pin "1") (pinfunction "S_1") (pintype "passive"))
      (node (ref "X3") (pin "4") (pinfunction "S_4") (pintype "passive"))
    )
    (net (code "31") (name "RECEIVE") (class "Default")
      (node (ref "IC1") (pin "13") (pinfunction "X_13") (pintype "bidirectional"))
      (node (ref "IC8") (pin "3") (pinfunction "IN+_A_3") (pintype "input"))
    )
    (net (code "32") (name "RECEIVE_E") (class "Default")
      (node (ref "IC1") (pin "11") (pinfunction "X3_11") (pintype "bidirectional"))
      (node (ref "IC1") (pin "2") (pinfunction "Y2_2") (pintype "input"))
      (node (ref "R15") (pin "1") (pinfunction "1_1") (pintype "passive"))
    )
    (net (code "33") (name "RECEIVE_N") (class "Default")
      (node (ref "IC1") (pin "1") (pinfunction "Y0_1") (pintype "input"))
      (node (ref "IC1") (pin "14") (pinfunction "X1_14") (pintype "bidirectional"))
      (node (ref "R11") (pin "1") (pinfunction "1_1") (pintype "passive"))
    )
    (net (code "34") (name "RECEIVE_S") (class "Default")
      (node (ref "IC1") (pin "12") (pinfunction "X0_12") (pintype "bidirectional"))
      (node (ref "IC1") (pin "5") (pinfunction "Y1_5") (pintype "input"))
      (node (ref "R13") (pin "1") (pinfunction "1_1") (pintype "passive"))
    )
    (net (code "35") (name "RECEIVE_W") (class "Default")
      (node (ref "IC1") (pin "15") (pinfunction "X2_15") (pintype "bidirectional"))
      (node (ref "IC1") (pin "4") (pinfunction "Y3_4") (pintype "input"))
      (node (ref "R17") (pin "1") (pinfunction "1_1") (pintype "passive"))
    )
    (net (code "36") (name "RELEASE_E") (class "Default")
      (node (ref "IC2") (pin "4") (pinfunction "Y3_4") (pintype "input"))
      (node (ref "Q4") (pin "1") (pinfunction "G_1") (pintype "passive"))
      (node (ref "R7") (pin "2") (pinfunction "2_2") (pintype "passive"))
    )
    (net (code "37") (name "RELEASE_N") (class "Default")
      (node (ref "IC2") (pin "5") (pinfunction "Y1_5") (pintype "input"))
      (node (ref "Q2") (pin "1") (pinfunction "G_1") (pintype "passive"))
      (node (ref "R6") (pin "2") (pinfunction "2_2") (pintype "passive"))
    )
    (net (code "38") (name "RELEASE_S") (class "Default")
      (node (ref "IC2") (pin "1") (pinfunction "Y0_1") (pintype "input"))
      (node (ref "Q3") (pin "1") (pinfunction "G_1") (pintype "passive"))
      (node (ref "R9") (pin "2") (pinfunction "2_2") (pintype "passive"))
    )
    (net (code "39") (name "RELEASE_W") (class "Default")
      (node (ref "IC2") (pin "2") (pinfunction "Y2_2") (pintype "input"))
      (node (ref "Q5") (pin "1") (pinfunction "G_1") (pintype "passive"))
      (node (ref "R8") (pin "2") (pinfunction "2_2") (pintype "passive"))
    )
    (net (code "40") (name "SCL1") (class "Default")
      (node (ref "IC5") (pin "17") (pinfunction "TCK/RPB8/SCL1/CTED10/PMD4/RB8_17") (pintype "bidirectional"))
      (node (ref "R18") (pin "2") (pinfunction "2_2") (pintype "passive"))
      (node (ref "X6") (pin "2") (pinfunction "S_2") (pintype "passive"))
    )
    (net (code "41") (name "SCL2") (class "Default")
      (node (ref "IC10") (pin "2") (pinfunction "SCL_2") (pintype "input"))
      (node (ref "IC5") (pin "7") (pinfunction "AN5/C1INA/C2INC/RTCC/RPB3/SCL2/PMWR/RB3_7") (pintype "bidirectional"))
      (node (ref "R29") (pin "2") (pinfunction "2_2") (pintype "passive"))
      (node (ref "X9") (pin "2") (pinfunction "S_2") (pintype "passive"))
    )
    (net (code "42") (name "SCLK") (class "Default")
      (node (ref "IC5") (pin "26") (pinfunction "AN9/C3INA/RPB15/SCK2/CTED6/PMCS1/RB15_26") (pintype "bidirectional"))
      (node (ref "X2") (pin "3") (pinfunction "S_3") (pintype "passive"))
    )
    (net (code "43") (name "SDA1") (class "Default")
      (node (ref "IC5") (pin "18") (pinfunction "TDO/RPB9/SDA1/CTED4/PMD3/RB9_18") (pintype "bidirectional"))
      (node (ref "R19") (pin "2") (pinfunction "2_2") (pintype "passive"))
      (node (ref "X6") (pin "1") (pinfunction "S_1") (pintype "passive"))
    )
    (net (code "44") (name "SDA2") (class "Default")
      (node (ref "IC10") (pin "3") (pinfunction "SDA_3") (pintype "bidirectional"))
      (node (ref "IC5") (pin "6") (pinfunction "AN4/C1INB/C2IND/RPB2/SDA2/CTED13/PMD2/RB2_6") (pintype "bidirectional"))
      (node (ref "R28") (pin "2") (pinfunction "2_2") (pintype "passive"))
      (node (ref "X9") (pin "1") (pinfunction "S_1") (pintype "passive"))
    )
    (net (code "45") (name "SIGNAL") (class "Default")
      (node (ref "IC2") (pin "13") (pinfunction "X_13") (pintype "bidirectional"))
      (node (ref "IC5") (pin "14") (pinfunction "TMS/RPB5/USBID/RB5_14") (pintype "bidirectional"))
      (node (ref "X8") (pin "3") (pinfunction "S_3") (pintype "passive"))
    )
    (net (code "46") (name "SIGNAL_E") (class "Default")
      (node (ref "IC2") (pin "15") (pinfunction "X2_15") (pintype "bidirectional"))
      (node (ref "IC7") (pin "2") (pinfunction "IN_A_2") (pintype "input"))
      (node (ref "R5") (pin "2") (pinfunction "2_2") (pintype "passive"))
    )
    (net (code "47") (name "SIGNAL_N") (class "Default")
      (node (ref "IC2") (pin "12") (pinfunction "X0_12") (pintype "bidirectional"))
      (node (ref "IC3") (pin "2") (pinfunction "IN_A_2") (pintype "input"))
      (node (ref "R3") (pin "2") (pinfunction "2_2") (pintype "passive"))
    )
    (net (code "48") (name "SIGNAL_S") (class "Default")
      (node (ref "IC2") (pin "14") (pinfunction "X1_14") (pintype "bidirectional"))
      (node (ref "IC3") (pin "4") (pinfunction "IN_B_4") (pintype "passive"))
      (node (ref "R4") (pin "2") (pinfunction "2_2") (pintype "passive"))
    )
    (net (code "49") (name "SIGNAL_W") (class "Default")
      (node (ref "IC2") (pin "11") (pinfunction "X3_11") (pintype "bidirectional"))
      (node (ref "IC7") (pin "4") (pinfunction "IN_B_4") (pintype "passive"))
      (node (ref "R2") (pin "2") (pinfunction "2_2") (pintype "passive"))
    )
    (net (code "50") (name "SOUTH") (class "Default")
      (node (ref "CON1") (pin "3") (pinfunction "P$3_3") (pintype "passive"))
      (node (ref "Q3") (pin "3") (pinfunction "D_3") (pintype "passive"))
      (node (ref "R12") (pin "2") (pinfunction "2_2") (pintype "passive"))
      (node (ref "R13") (pin "2") (pinfunction "2_2") (pintype "passive"))
    )
    (net (code "51") (name "STAGE_1") (class "Default")
      (node (ref "C22") (pin "2") (pinfunction "2_2") (pintype "passive"))
      (node (ref "IC8") (pin "1") (pinfunction "OUT_A_1") (pintype "input"))
      (node (ref "R20") (pin "2") (pinfunction "2_2") (pintype "passive"))
    )
    (net (code "52") (name "STAGE_2") (class "Default")
      (node (ref "C26") (pin "2") (pinfunction "2_2") (pintype "passive"))
      (node (ref "IC10") (pin "7") (pinfunction "P0B_7") (pintype "passive"))
      (node (ref "IC8") (pin "7") (pinfunction "OUT_B_7") (pintype "input"))
    )
    (net (code "53") (name "VBUS") (class "Default")
      (node (ref "IC5") (pin "15") (pinfunction "VBUS_15") (pintype "bidirectional"))
      (node (ref "X4") (pin "+5V") (pinfunction "+5V_+5V") (pintype "passive"))
      (node (ref "X7") (pin "3") (pinfunction "S_3") (pintype "passive"))
    )
    (net (code "54") (name "WEST") (class "Default")
      (node (ref "CON1") (pin "7") (pinfunction "P$7_7") (pintype "passive"))
      (node (ref "Q5") (pin "3") (pinfunction "D_3") (pintype "passive"))
      (node (ref "R16") (pin "2") (pinfunction "2_2") (pintype "passive"))
      (node (ref "R17") (pin "2") (pinfunction "2_2") (pintype "passive"))
    )
    (net (code "55") (name "ZCD") (class "Default")
      (node (ref "IC5") (pin "16") (pinfunction "TDI/RPB7/CTED3/PMD5/INT0/RB7_16") (pintype "bidirectional"))
      (node (ref "IC6") (pin "1") (pinfunction "VOUT_1") (pintype "output"))
      (node (ref "X5") (pin "3") (pinfunction "S_3") (pintype "passive"))
    )
    (net (code "56") (name "unconnected-(IC3-NC-Pad1)") (class "Default")
      (node (ref "IC3") (pin "1") (pinfunction "NC_1") (pintype "no_connect"))
    )
    (net (code "57") (name "unconnected-(IC3-NC-Pad8)") (class "Default")
      (node (ref "IC3") (pin "8") (pinfunction "NC_8") (pintype "no_connect"))
    )
    (net (code "58") (name "unconnected-(IC7-NC-Pad1)") (class "Default")
      (node (ref "IC7") (pin "1") (pinfunction "NC_1") (pintype "no_connect"))
    )
    (net (code "59") (name "unconnected-(IC7-NC-Pad8)") (class "Default")
      (node (ref "IC7") (pin "8") (pinfunction "NC_8") (pintype "no_connect"))
    )
    (net (code "60") (name "unconnected-(IC9-PWRGD-Pad4)") (class "Default")
      (node (ref "IC9") (pin "4") (pinfunction "PWRGD_4") (pintype "output"))
    )
    (net (code "61") (name "~{MCLR}") (class "Default")
      (node (ref "IC5") (pin "1") (pinfunction "~{MCLR}_1") (pintype "input"))
      (node (ref "R27") (pin "2") (pinfunction "2_2") (pintype "passive"))
      (node (ref "X3") (pin "1") (pinfunction "S_1") (pintype "passive"))
    )
  )
)
